# Switching_Bridge.net
KiCad netlist of a schematic drawn in Altium Designer
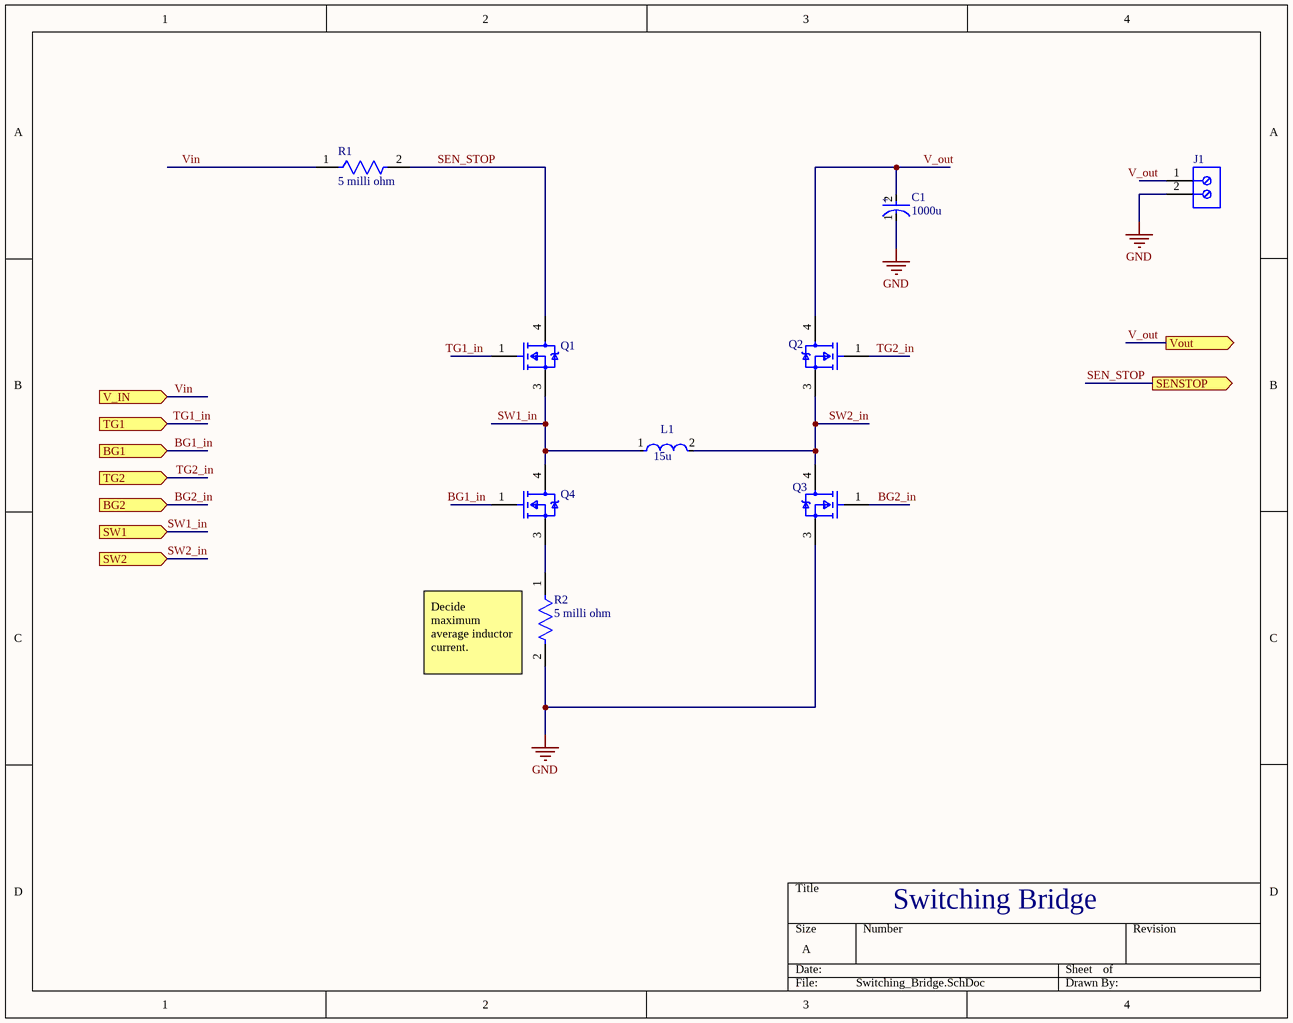
[diagram p0: Switching_Bridge.SchDoc]

(export (version "E")
  (design (tool "Eeschema 10.0.6"))
  (components
    (comp (ref "C1")
      (value "1000u")
      (footprint "FP-RAD-TH-D_10_0_5-L_25_2-MFG")
      (description "Aluminum Electrolytic Capacitors (Radial Lead Type) 1000uF ±20% 35V")
      (fields (field (name "VOLTAGE") "25V") (field (name "TOLERANCE") "20%"))
      (libsource (lib "Altium Content Vault") (part "a00bbbee19879c290e62620ae7e47b1"))
    )
    (comp (ref "J1")
      (value "691134710002")
      (footprint "691134710002")
      (description "Wire-To-Board Terminal Block, 5mm Pitch, Horizontal, Screw, 2 Poles")
      (libsource (lib "Altium Content Vault") (part "TBL - 1R - 02P - Screw"))
    )
    (comp (ref "L1")
      (value "15u")
      (footprint "FP-SRP1038WA-MFG")
      (description "IND,11X10X3.8MM,3.3UH20%,15A,SHD")
      (libsource (lib "Altium Content Vault") (part "725321dda6339637d4d059423bc1c3c"))
    )
    (comp (ref "Q1")
      (value "IRF540NSTRLPBF")
      (footprint "FP-PG-TO263-3-MFG")
      (description "IRF540NSTRLPBF Transistor MOSFET N Channel 100 Volt 33 Amp 3-Pin 2+ Tab D2pak Tape And Reel")
      (libsource (lib "Altium Content Vault") (part "880dca94e4e73acafd9c8cab4fdbffa"))
    )
    (comp (ref "Q2")
      (value "IRF540NSTRLPBF")
      (footprint "FP-PG-TO263-3-MFG")
      (description "IRF540NSTRLPBF Transistor MOSFET N Channel 100 Volt 33 Amp 3-Pin 2+ Tab D2pak Tape And Reel")
      (libsource (lib "Altium Content Vault") (part "880dca94e4e73acafd9c8cab4fdbffa"))
    )
    (comp (ref "Q3")
      (value "IRF540NSTRLPBF")
      (footprint "FP-PG-TO263-3-MFG")
      (description "IRF540NSTRLPBF Transistor MOSFET N Channel 100 Volt 33 Amp 3-Pin 2+ Tab D2pak Tape And Reel")
      (libsource (lib "Altium Content Vault") (part "880dca94e4e73acafd9c8cab4fdbffa"))
    )
    (comp (ref "Q4")
      (value "IRF540NSTRLPBF")
      (footprint "FP-PG-TO263-3-MFG")
      (description "IRF540NSTRLPBF Transistor MOSFET N Channel 100 Volt 33 Amp 3-Pin 2+ Tab D2pak Tape And Reel")
      (libsource (lib "Altium Content Vault") (part "880dca94e4e73acafd9c8cab4fdbffa"))
    )
    (comp (ref "R1")
      (value "5 milli ohm")
      (footprint "FP-WSLP2512-0R001-0R0049-MFG")
      (libsource (lib "Altium Content Vault") (part "1029c3af85768c4190bb7ad29bc67b5"))
    )
    (comp (ref "R2")
      (value "5 milli ohm")
      (footprint "FP-WSLP2512-0R001-0R0049-MFG")
      (libsource (lib "Altium Content Vault") (part "1029c3af85768c4190bb7ad29bc67b5"))
    )
  )
  (nets
    (net (code "2") (name "/BG1_in") (class "Default")
      (node (ref "Q4") (pin "1") (pinfunction "GATE_1") (pintype "passive"))
    )
    (net (code "3") (name "/BG2_in") (class "Default")
      (node (ref "Q3") (pin "1") (pinfunction "GATE_1") (pintype "passive"))
    )
    (net (code "4") (name "/SEN_STOP") (class "Default")
      (node (ref "Q1") (pin "4") (pinfunction "DRAIN_4") (pintype "passive"))
      (node (ref "R1") (pin "2") (pinfunction "2_2") (pintype "passive"))
    )
    (net (code "5") (name "/SW1_in") (class "Default")
      (node (ref "L1") (pin "1") (pinfunction "1_1") (pintype "passive"))
      (node (ref "Q1") (pin "3") (pinfunction "SOURCE_3") (pintype "passive"))
      (node (ref "Q4") (pin "4") (pinfunction "DRAIN_4") (pintype "passive"))
    )
    (net (code "6") (name "/SW2_in") (class "Default")
      (node (ref "L1") (pin "2") (pinfunction "2_2") (pintype "passive"))
      (node (ref "Q2") (pin "3") (pinfunction "SOURCE_3") (pintype "passive"))
      (node (ref "Q3") (pin "4") (pinfunction "DRAIN_4") (pintype "passive"))
    )
    (net (code "7") (name "/TG1_in") (class "Default")
      (node (ref "Q1") (pin "1") (pinfunction "GATE_1") (pintype "passive"))
    )
    (net (code "8") (name "/TG2_in") (class "Default")
      (node (ref "Q2") (pin "1") (pinfunction "GATE_1") (pintype "passive"))
    )
    (net (code "9") (name "/V_out") (class "Default")
      (node (ref "C1") (pin "2") (pinfunction "A_2") (pintype "passive"))
      (node (ref "J1") (pin "1") (pinfunction "1_1") (pintype "passive"))
      (node (ref "Q2") (pin "4") (pinfunction "DRAIN_4") (pintype "passive"))
    )
    (net (code "10") (name "/Vin") (class "Default")
      (node (ref "R1") (pin "1") (pinfunction "1_1") (pintype "passive"))
    )
    (net (code "11") (name "GND") (class "Default")
      (node (ref "C1") (pin "1") (pinfunction "C_1") (pintype "passive"))
      (node (ref "J1") (pin "2") (pinfunction "2_2") (pintype "passive"))
      (node (ref "Q3") (pin "3") (pinfunction "SOURCE_3") (pintype "passive"))
      (node (ref "R2") (pin "2") (pinfunction "2_2") (pintype "passive"))
    )
    (net (code "12") (name "Net-(Q4-SOURCE)") (class "Default")
      (node (ref "Q4") (pin "3") (pinfunction "SOURCE_3") (pintype "passive"))
      (node (ref "R2") (pin "1") (pinfunction "1_1") (pintype "passive"))
    )
  )
)
